# 1_Sheet_1.net
KiCad netlist of a schematic drawn in Altium Designer
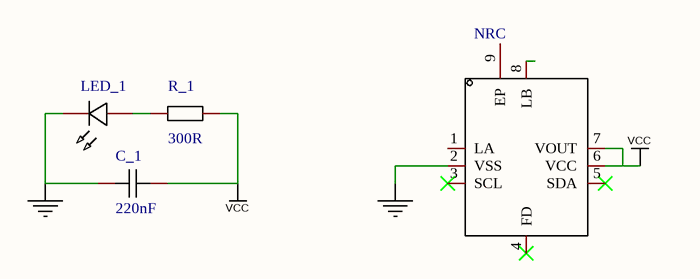
[diagram p0: 1_Sheet_1.schdoc]

(export (version "E")
  (design (tool "Eeschema 10.0.6"))
  (components
    (comp (ref "C_1")
      (value "220nF")
      (fields (field (name "Comment") "CAP_0603"))
      (libsource (lib "altium-import") (part "root_0_CAP_0603_"))
    )
    (comp (ref "LED_1") (value "LED_0603-R") (libsource (lib "altium-import") (part "root_2_LED_0603-R_")))
    (comp (ref "NRC")
      (value "NT3H1101W0FHKH")
      (fields (field (name "MANUFACTURER") "NXP(恩智浦)"))
      (libsource (lib "altium-import") (part "root_0_NT3H1101W0FHKH_"))
    )
    (comp (ref "R_1")
      (value "300R")
      (fields (field (name "Comment") "Res_0603"))
      (libsource (lib "altium-import") (part "root_0_Res_0603_"))
    )
  )
  (nets
    (net (code "1") (name "<NO NET>") (class "Default")
      (node (ref "C_1") (pin "1") (pinfunction "1_1") (pintype "passive"))
      (node (ref "LED_1") (pin "1") (pinfunction "C_1") (pintype "passive"))
      (node (ref "NRC") (pin "2") (pinfunction "VSS_2") (pintype "passive"))
    )
    (net (code "2") (name "Net-(LED_1-A)") (class "Default")
      (node (ref "LED_1") (pin "2") (pinfunction "A_2") (pintype "passive"))
      (node (ref "R_1") (pin "1") (pinfunction "1_1") (pintype "passive"))
    )
    (net (code "3") (name "VCC") (class "Default")
      (node (ref "C_1") (pin "2") (pinfunction "2_2") (pintype "passive"))
      (node (ref "NRC") (pin "6") (pinfunction "VCC_6") (pintype "passive"))
      (node (ref "NRC") (pin "7") (pinfunction "VOUT_7") (pintype "passive"))
      (node (ref "R_1") (pin "2") (pinfunction "2_2") (pintype "passive"))
    )
    (net (code "4") (name "unconnected-(NRC-EP-Pad9)") (class "Default")
      (node (ref "NRC") (pin "9") (pinfunction "EP_9") (pintype "passive"))
    )
    (net (code "5") (name "unconnected-(NRC-FD-Pad4)") (class "Default")
      (node (ref "NRC") (pin "4") (pinfunction "FD_4") (pintype "passive+no_connect"))
    )
    (net (code "6") (name "unconnected-(NRC-LA-Pad1)") (class "Default")
      (node (ref "NRC") (pin "1") (pinfunction "LA_1") (pintype "passive"))
    )
    (net (code "7") (name "unconnected-(NRC-LB-Pad8)") (class "Default")
      (node (ref "NRC") (pin "8") (pinfunction "LB_8") (pintype "passive"))
    )
    (net (code "8") (name "unconnected-(NRC-SCL-Pad3)") (class "Default")
      (node (ref "NRC") (pin "3") (pinfunction "SCL_3") (pintype "passive+no_connect"))
    )
    (net (code "9") (name "unconnected-(NRC-SDA-Pad5)") (class "Default")
      (node (ref "NRC") (pin "5") (pinfunction "SDA_5") (pintype "passive+no_connect"))
    )
  )
)
